# OTHER.net
KiCad netlist of a schematic drawn in Altium Designer
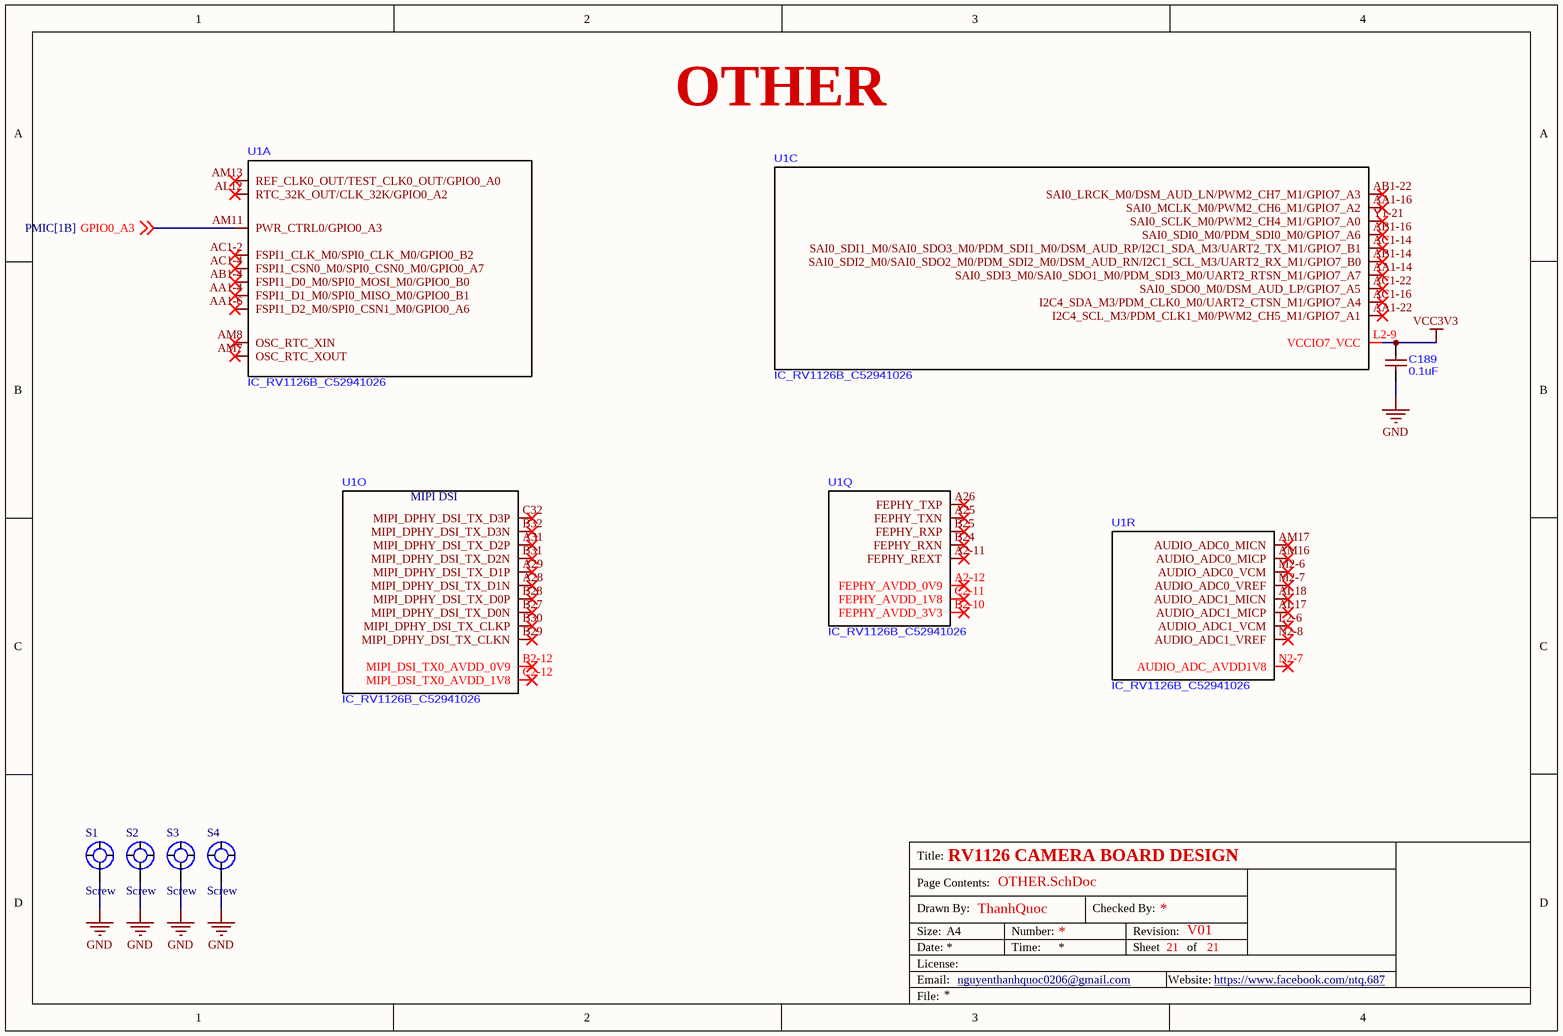
[diagram p0: OTHER.SchDoc]

(export (version "E")
  (design (tool "Eeschema 10.0.6"))
  (components
    (comp (ref "C189")
      (value "0.1uF")
      (footprint "C0201")
      (description "0.1uF ±10% 6.3V Ceramic Capacitor X5R 0201")
      (libsource (lib "Schlib1") (part "CAP_100nF-6.3V-10%-0201_1"))
    )
    (comp (ref "S1") (value "Screw") (footprint "SCREW 3.0") (libsource (lib "Schlib1") (part "Screw")))
    (comp (ref "S2") (value "Screw") (footprint "SCREW 3.0") (libsource (lib "Schlib1") (part "Screw")))
    (comp (ref "S3") (value "Screw") (footprint "SCREW 3.0") (libsource (lib "Schlib1") (part "Screw")))
    (comp (ref "S4") (value "Screw") (footprint "SCREW 3.0") (libsource (lib "Schlib1") (part "Screw")))
    (comp (ref "U1")
      (value "IC_RV1126B_C52941026")
      (footprint "CCSP-491_L14.0-W14.0-TL_RV1126B")
      (libsource (lib "Schlib1") (part "IC_RV1126B_C52941026"))
    )
  )
  (nets
    (net (code "1") (name "GND") (class "Default")
      (node (ref "C189") (pin "1") (pinfunction "1_1") (pintype "passive"))
      (node (ref "S1") (pin "1") (pinfunction "1_1") (pintype "passive"))
      (node (ref "S2") (pin "1") (pinfunction "1_1") (pintype "passive"))
      (node (ref "S3") (pin "1") (pinfunction "1_1") (pintype "passive"))
      (node (ref "S4") (pin "1") (pinfunction "1_1") (pintype "passive"))
    )
    (net (code "2") (name "GPIO0_A3") (class "Default")
      (node (ref "U1") (pin "AM11") (pinfunction "PWR_CTRL0/GPIO0_A3_AM11") (pintype "passive"))
    )
    (net (code "3") (name "VCC3V3") (class "Default")
      (node (ref "C189") (pin "2") (pinfunction "2_2") (pintype "passive"))
      (node (ref "U1") (pin "L2-9") (pinfunction "VCCIO7_VCC_L2-9") (pintype "passive"))
    )
    (net (code "4") (name "unconnected-(U1A-FSPI1_CLK_M0{slash}SPI0_CLK_M0{slash}GPIO0_B2-PadAC1-2)") (class "Default")
      (node (ref "U1") (pin "AC1-2") (pinfunction "FSPI1_CLK_M0/SPI0_CLK_M0/GPIO0_B2_AC1-2") (pintype "passive+no_connect"))
    )
    (net (code "5") (name "unconnected-(U1A-FSPI1_CSN0_M0{slash}SPI0_CSN0_M0{slash}GPIO0_A7-PadAC1-4)") (class "Default")
      (node (ref "U1") (pin "AC1-4") (pinfunction "FSPI1_CSN0_M0/SPI0_CSN0_M0/GPIO0_A7_AC1-4") (pintype "passive+no_connect"))
    )
    (net (code "6") (name "unconnected-(U1A-FSPI1_D0_M0{slash}SPI0_MOSI_M0{slash}GPIO0_B0-PadAB1-4)") (class "Default")
      (node (ref "U1") (pin "AB1-4") (pinfunction "FSPI1_D0_M0/SPI0_MOSI_M0/GPIO0_B0_AB1-4") (pintype "passive+no_connect"))
    )
    (net (code "7") (name "unconnected-(U1A-FSPI1_D1_M0{slash}SPI0_MISO_M0{slash}GPIO0_B1-PadAA1-4)") (class "Default")
      (node (ref "U1") (pin "AA1-4") (pinfunction "FSPI1_D1_M0/SPI0_MISO_M0/GPIO0_B1_AA1-4") (pintype "passive+no_connect"))
    )
    (net (code "8") (name "unconnected-(U1A-FSPI1_D2_M0{slash}SPI0_CSN1_M0{slash}GPIO0_A6-PadAA1-6)") (class "Default")
      (node (ref "U1") (pin "AA1-6") (pinfunction "FSPI1_D2_M0/SPI0_CSN1_M0/GPIO0_A6_AA1-6") (pintype "passive+no_connect"))
    )
    (net (code "9") (name "unconnected-(U1A-OSC_RTC_XIN-PadAM8)") (class "Default")
      (node (ref "U1") (pin "AM8") (pinfunction "OSC_RTC_XIN_AM8") (pintype "passive+no_connect"))
    )
    (net (code "10") (name "unconnected-(U1A-OSC_RTC_XOUT-PadAM7)") (class "Default")
      (node (ref "U1") (pin "AM7") (pinfunction "OSC_RTC_XOUT_AM7") (pintype "passive+no_connect"))
    )
    (net (code "11") (name "unconnected-(U1A-REF_CLK0_OUT{slash}TEST_CLK0_OUT{slash}GPIO0_A0-PadAM13)") (class "Default")
      (node (ref "U1") (pin "AM13") (pinfunction "REF_CLK0_OUT/TEST_CLK0_OUT/GPIO0_A0_AM13") (pintype "passive+no_connect"))
    )
    (net (code "12") (name "unconnected-(U1A-RTC_32K_OUT{slash}CLK_32K{slash}GPIO0_A2-PadAL12)") (class "Default")
      (node (ref "U1") (pin "AL12") (pinfunction "RTC_32K_OUT/CLK_32K/GPIO0_A2_AL12") (pintype "passive+no_connect"))
    )
    (net (code "13") (name "unconnected-(U1C-I2C4_SCL_M3{slash}PDM_CLK1_M0{slash}PWM2_CH5_M1{slash}GPIO7_A1-PadAA1-22)") (class "Default")
      (node (ref "U1") (pin "AA1-22") (pinfunction "I2C4_SCL_M3/PDM_CLK1_M0/PWM2_CH5_M1/GPIO7_A1_AA1-22") (pintype "passive+no_connect"))
    )
    (net (code "14") (name "unconnected-(U1C-I2C4_SDA_M3{slash}PDM_CLK0_M0{slash}UART2_CTSN_M1{slash}GPIO7_A4-PadAC1-16)") (class "Default")
      (node (ref "U1") (pin "AC1-16") (pinfunction "I2C4_SDA_M3/PDM_CLK0_M0/UART2_CTSN_M1/GPIO7_A4_AC1-16") (pintype "passive+no_connect"))
    )
    (net (code "15") (name "unconnected-(U1C-SAI0_LRCK_M0{slash}DSM_AUD_LN{slash}PWM2_CH7_M1{slash}GPIO7_A3-PadAB1-22)") (class "Default")
      (node (ref "U1") (pin "AB1-22") (pinfunction "SAI0_LRCK_M0/DSM_AUD_LN/PWM2_CH7_M1/GPIO7_A3_AB1-22") (pintype "passive+no_connect"))
    )
    (net (code "16") (name "unconnected-(U1C-SAI0_MCLK_M0{slash}PWM2_CH6_M1{slash}GPIO7_A2-PadAA1-16)") (class "Default")
      (node (ref "U1") (pin "AA1-16") (pinfunction "SAI0_MCLK_M0/PWM2_CH6_M1/GPIO7_A2_AA1-16") (pintype "passive+no_connect"))
    )
    (net (code "17") (name "unconnected-(U1C-SAI0_SCLK_M0{slash}PWM2_CH4_M1{slash}GPIO7_A0-PadY1-21)") (class "Default")
      (node (ref "U1") (pin "Y1-21") (pinfunction "SAI0_SCLK_M0/PWM2_CH4_M1/GPIO7_A0_Y1-21") (pintype "passive+no_connect"))
    )
    (net (code "18") (name "unconnected-(U1C-SAI0_SDI0_M0{slash}PDM_SDI0_M0{slash}GPIO7_A6-PadAB1-16)") (class "Default")
      (node (ref "U1") (pin "AB1-16") (pinfunction "SAI0_SDI0_M0/PDM_SDI0_M0/GPIO7_A6_AB1-16") (pintype "passive+no_connect"))
    )
    (net (code "19") (name "unconnected-(U1C-SAI0_SDI1_M0{slash}SAI0_SDO3_M0{slash}PDM_SDI1_M0{slash}DSM_AUD_RP{slash}I2C1_SDA_M3{slash}UART2_TX_M1{slash}GPIO7_B1-PadAC1-14)") (class "Default")
      (node (ref "U1") (pin "AC1-14") (pinfunction "SAI0_SDI1_M0/SAI0_SDO3_M0/PDM_SDI1_M0/DSM_AUD_RP/I2C1_SDA_M3/UART2_TX_M1/GPIO7_B1_AC1-14") (pintype "passive+no_connect"))
    )
    (net (code "20") (name "unconnected-(U1C-SAI0_SDI2_M0{slash}SAI0_SDO2_M0{slash}PDM_SDI2_M0{slash}DSM_AUD_RN{slash}I2C1_SCL_M3{slash}UART2_RX_M1{slash}GPIO7_B0-PadAB1-14)") (class "Default")
      (node (ref "U1") (pin "AB1-14") (pinfunction "SAI0_SDI2_M0/SAI0_SDO2_M0/PDM_SDI2_M0/DSM_AUD_RN/I2C1_SCL_M3/UART2_RX_M1/GPIO7_B0_AB1-14") (pintype "passive+no_connect"))
    )
    (net (code "21") (name "unconnected-(U1C-SAI0_SDI3_M0{slash}SAI0_SDO1_M0{slash}PDM_SDI3_M0{slash}UART2_RTSN_M1{slash}GPIO7_A7-PadAA1-14)") (class "Default")
      (node (ref "U1") (pin "AA1-14") (pinfunction "SAI0_SDI3_M0/SAI0_SDO1_M0/PDM_SDI3_M0/UART2_RTSN_M1/GPIO7_A7_AA1-14") (pintype "passive+no_connect"))
    )
    (net (code "22") (name "unconnected-(U1C-SAI0_SDO0_M0{slash}DSM_AUD_LP{slash}GPIO7_A5-PadAC1-22)") (class "Default")
      (node (ref "U1") (pin "AC1-22") (pinfunction "SAI0_SDO0_M0/DSM_AUD_LP/GPIO7_A5_AC1-22") (pintype "passive+no_connect"))
    )
    (net (code "23") (name "unconnected-(U1O-MIPI_DPHY_DSI_TX_CLKN-PadB29)") (class "Default")
      (node (ref "U1") (pin "B29") (pinfunction "MIPI_DPHY_DSI_TX_CLKN_B29") (pintype "passive+no_connect"))
    )
    (net (code "24") (name "unconnected-(U1O-MIPI_DPHY_DSI_TX_CLKP-PadB30)") (class "Default")
      (node (ref "U1") (pin "B30") (pinfunction "MIPI_DPHY_DSI_TX_CLKP_B30") (pintype "passive+no_connect"))
    )
    (net (code "25") (name "unconnected-(U1O-MIPI_DPHY_DSI_TX_D0N-PadB27)") (class "Default")
      (node (ref "U1") (pin "B27") (pinfunction "MIPI_DPHY_DSI_TX_D0N_B27") (pintype "passive+no_connect"))
    )
    (net (code "26") (name "unconnected-(U1O-MIPI_DPHY_DSI_TX_D0P-PadB28)") (class "Default")
      (node (ref "U1") (pin "B28") (pinfunction "MIPI_DPHY_DSI_TX_D0P_B28") (pintype "passive+no_connect"))
    )
    (net (code "27") (name "unconnected-(U1O-MIPI_DPHY_DSI_TX_D1N-PadA28)") (class "Default")
      (node (ref "U1") (pin "A28") (pinfunction "MIPI_DPHY_DSI_TX_D1N_A28") (pintype "passive+no_connect"))
    )
    (net (code "28") (name "unconnected-(U1O-MIPI_DPHY_DSI_TX_D1P-PadA29)") (class "Default")
      (node (ref "U1") (pin "A29") (pinfunction "MIPI_DPHY_DSI_TX_D1P_A29") (pintype "passive+no_connect"))
    )
    (net (code "29") (name "unconnected-(U1O-MIPI_DPHY_DSI_TX_D2N-PadB31)") (class "Default")
      (node (ref "U1") (pin "B31") (pinfunction "MIPI_DPHY_DSI_TX_D2N_B31") (pintype "passive+no_connect"))
    )
    (net (code "30") (name "unconnected-(U1O-MIPI_DPHY_DSI_TX_D2P-PadA31)") (class "Default")
      (node (ref "U1") (pin "A31") (pinfunction "MIPI_DPHY_DSI_TX_D2P_A31") (pintype "passive+no_connect"))
    )
    (net (code "31") (name "unconnected-(U1O-MIPI_DPHY_DSI_TX_D3N-PadB32)") (class "Default")
      (node (ref "U1") (pin "B32") (pinfunction "MIPI_DPHY_DSI_TX_D3N_B32") (pintype "passive+no_connect"))
    )
    (net (code "32") (name "unconnected-(U1O-MIPI_DPHY_DSI_TX_D3P-PadC32)") (class "Default")
      (node (ref "U1") (pin "C32") (pinfunction "MIPI_DPHY_DSI_TX_D3P_C32") (pintype "passive+no_connect"))
    )
    (net (code "33") (name "unconnected-(U1O-MIPI_DSI_TX0_AVDD_0V9-PadB2-12)") (class "Default")
      (node (ref "U1") (pin "B2-12") (pinfunction "MIPI_DSI_TX0_AVDD_0V9_B2-12") (pintype "passive+no_connect"))
    )
    (net (code "34") (name "unconnected-(U1O-MIPI_DSI_TX0_AVDD_1V8-PadC2-12)") (class "Default")
      (node (ref "U1") (pin "C2-12") (pinfunction "MIPI_DSI_TX0_AVDD_1V8_C2-12") (pintype "passive+no_connect"))
    )
    (net (code "35") (name "unconnected-(U1Q-FEPHY_AVDD_0V9-PadA2-12)") (class "Default")
      (node (ref "U1") (pin "A2-12") (pinfunction "FEPHY_AVDD_0V9_A2-12") (pintype "passive+no_connect"))
    )
    (net (code "36") (name "unconnected-(U1Q-FEPHY_AVDD_1V8-PadC2-11)") (class "Default")
      (node (ref "U1") (pin "C2-11") (pinfunction "FEPHY_AVDD_1V8_C2-11") (pintype "passive+no_connect"))
    )
    (net (code "37") (name "unconnected-(U1Q-FEPHY_AVDD_3V3-PadB2-10)") (class "Default")
      (node (ref "U1") (pin "B2-10") (pinfunction "FEPHY_AVDD_3V3_B2-10") (pintype "passive+no_connect"))
    )
    (net (code "38") (name "unconnected-(U1Q-FEPHY_REXT-PadA2-11)") (class "Default")
      (node (ref "U1") (pin "A2-11") (pinfunction "FEPHY_REXT_A2-11") (pintype "passive+no_connect"))
    )
    (net (code "39") (name "unconnected-(U1Q-FEPHY_RXN-PadB24)") (class "Default")
      (node (ref "U1") (pin "B24") (pinfunction "FEPHY_RXN_B24") (pintype "passive+no_connect"))
    )
    (net (code "40") (name "unconnected-(U1Q-FEPHY_RXP-PadB25)") (class "Default")
      (node (ref "U1") (pin "B25") (pinfunction "FEPHY_RXP_B25") (pintype "passive+no_connect"))
    )
    (net (code "41") (name "unconnected-(U1Q-FEPHY_TXN-PadA25)") (class "Default")
      (node (ref "U1") (pin "A25") (pinfunction "FEPHY_TXN_A25") (pintype "passive+no_connect"))
    )
    (net (code "42") (name "unconnected-(U1Q-FEPHY_TXP-PadA26)") (class "Default")
      (node (ref "U1") (pin "A26") (pinfunction "FEPHY_TXP_A26") (pintype "passive+no_connect"))
    )
    (net (code "43") (name "unconnected-(U1R-AUDIO_ADC0_MICN-PadAM17)") (class "Default")
      (node (ref "U1") (pin "AM17") (pinfunction "AUDIO_ADC0_MICN_AM17") (pintype "passive+no_connect"))
    )
    (net (code "44") (name "unconnected-(U1R-AUDIO_ADC0_MICP-PadAM16)") (class "Default")
      (node (ref "U1") (pin "AM16") (pinfunction "AUDIO_ADC0_MICP_AM16") (pintype "passive+no_connect"))
    )
    (net (code "45") (name "unconnected-(U1R-AUDIO_ADC0_VCM-PadM2-6)") (class "Default")
      (node (ref "U1") (pin "M2-6") (pinfunction "AUDIO_ADC0_VCM_M2-6") (pintype "passive+no_connect"))
    )
    (net (code "46") (name "unconnected-(U1R-AUDIO_ADC0_VREF-PadM2-7)") (class "Default")
      (node (ref "U1") (pin "M2-7") (pinfunction "AUDIO_ADC0_VREF_M2-7") (pintype "passive+no_connect"))
    )
    (net (code "47") (name "unconnected-(U1R-AUDIO_ADC1_MICN-PadAL18)") (class "Default")
      (node (ref "U1") (pin "AL18") (pinfunction "AUDIO_ADC1_MICN_AL18") (pintype "passive+no_connect"))
    )
    (net (code "48") (name "unconnected-(U1R-AUDIO_ADC1_MICP-PadAL17)") (class "Default")
      (node (ref "U1") (pin "AL17") (pinfunction "AUDIO_ADC1_MICP_AL17") (pintype "passive+no_connect"))
    )
    (net (code "49") (name "unconnected-(U1R-AUDIO_ADC1_VCM-PadL2-6)") (class "Default")
      (node (ref "U1") (pin "L2-6") (pinfunction "AUDIO_ADC1_VCM_L2-6") (pintype "passive+no_connect"))
    )
    (net (code "50") (name "unconnected-(U1R-AUDIO_ADC1_VREF-PadN2-8)") (class "Default")
      (node (ref "U1") (pin "N2-8") (pinfunction "AUDIO_ADC1_VREF_N2-8") (pintype "passive+no_connect"))
    )
    (net (code "51") (name "unconnected-(U1R-AUDIO_ADC_AVDD1V8-PadN2-7)") (class "Default")
      (node (ref "U1") (pin "N2-7") (pinfunction "AUDIO_ADC_AVDD1V8_N2-7") (pintype "passive+no_connect"))
    )
  )
)
